# Con_Mic_Module_no_gain.net
KiCad netlist of a schematic drawn in Altium Designer
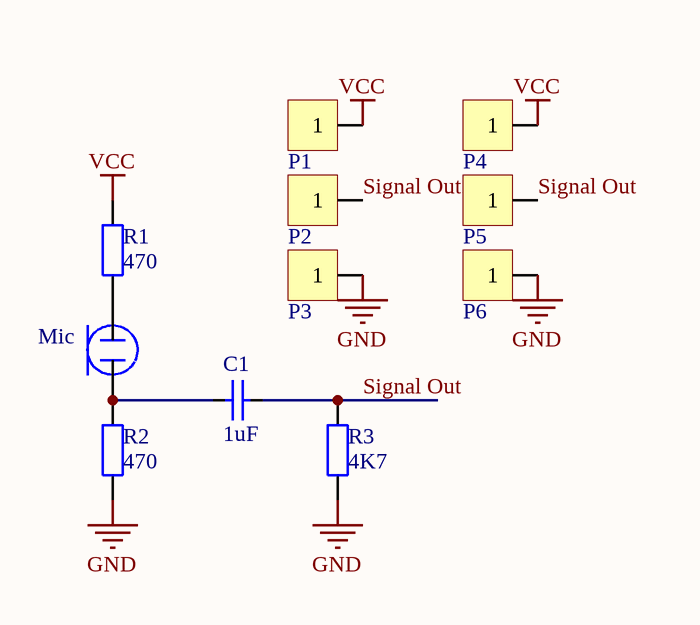
[diagram p0: Con_Mic_Module(no gain).SchDoc]

(export (version "E")
  (design (tool "Eeschema 10.0.6"))
  (components
    (comp (ref "C1")
      (value "1uF")
      (footprint "CAP_0805")
      (description "Capacitor")
      (fields (field (name "Comment") "Cap_0805"))
      (libsource (lib "Integrated_Library") (part "Cap_0805"))
    )
    (comp (ref "Mic")
      (value "Mic")
      (footprint "Con_Mic_9.6mm")
      (description "Condenser Microphone")
      (libsource (lib "Integrated_Library") (part "Con_Mic_9.7mm"))
    )
    (comp (ref "P1")
      (value "Pad1X1_1.27")
      (footprint "Pad1X1_1.27")
      (description "Header")
      (libsource (lib "Integrated_Library") (part "Pad1X1_1.27"))
    )
    (comp (ref "P2")
      (value "Pad1X1_1.27")
      (footprint "Pad1X1_1.27")
      (description "Header")
      (libsource (lib "Integrated_Library") (part "Pad1X1_1.27"))
    )
    (comp (ref "P3")
      (value "Pad1X1_1.27")
      (footprint "Pad1X1_1.27")
      (description "Header")
      (libsource (lib "Integrated_Library") (part "Pad1X1_1.27"))
    )
    (comp (ref "P4")
      (value "HDR1X1_180_2.54")
      (footprint "HDR1X1_180_2.54")
      (description "Header")
      (libsource (lib "Integrated_Library") (part "HDR1X1_180_2.54"))
    )
    (comp (ref "P5")
      (value "HDR1X1_180_2.54")
      (footprint "HDR1X1_180_2.54")
      (description "Header")
      (libsource (lib "Integrated_Library") (part "HDR1X1_180_2.54"))
    )
    (comp (ref "P6")
      (value "HDR1X1_180_2.54")
      (footprint "HDR1X1_180_2.54")
      (description "Header")
      (libsource (lib "Integrated_Library") (part "HDR1X1_180_2.54"))
    )
    (comp (ref "R1")
      (value "470")
      (footprint "RES_0805")
      (description "Resistor")
      (fields (field (name "Comment") "Res_0805"))
      (libsource (lib "Integrated_Library") (part "Res_0805"))
    )
    (comp (ref "R2")
      (value "470")
      (footprint "RES_0805")
      (description "Resistor")
      (fields (field (name "Comment") "Res_0805"))
      (libsource (lib "Integrated_Library") (part "Res_0805"))
    )
    (comp (ref "R3")
      (value "4K7")
      (footprint "RES_0805")
      (description "Resistor")
      (fields (field (name "Comment") "Res_0805"))
      (libsource (lib "Integrated_Library") (part "Res_0805"))
    )
  )
  (nets
    (net (code "1") (name "/Signal Out") (class "Default")
      (node (ref "C1") (pin "2") (pinfunction "2_2") (pintype "passive"))
      (node (ref "P2") (pin "1") (pinfunction "1_1") (pintype "passive"))
      (node (ref "P5") (pin "1") (pinfunction "1_1") (pintype "passive"))
      (node (ref "R3") (pin "2") (pinfunction "2_2") (pintype "passive"))
    )
    (net (code "2") (name "GND") (class "Default")
      (node (ref "P3") (pin "1") (pinfunction "1_1") (pintype "passive"))
      (node (ref "P6") (pin "1") (pinfunction "1_1") (pintype "passive"))
      (node (ref "R2") (pin "1") (pinfunction "1_1") (pintype "passive"))
      (node (ref "R3") (pin "1") (pinfunction "1_1") (pintype "passive"))
    )
    (net (code "3") (name "Net-(Mic-FlexiblePlat)") (class "Default")
      (node (ref "Mic") (pin "1") (pinfunction "FlexiblePlat_1") (pintype "passive"))
      (node (ref "R1") (pin "1") (pinfunction "1_1") (pintype "passive"))
    )
    (net (code "4") (name "Net-(Mic-RigidPlat)") (class "Default")
      (node (ref "C1") (pin "1") (pinfunction "1_1") (pintype "passive"))
      (node (ref "Mic") (pin "2") (pinfunction "RigidPlat_2") (pintype "passive"))
      (node (ref "R2") (pin "2") (pinfunction "2_2") (pintype "passive"))
    )
    (net (code "5") (name "VCC") (class "Default")
      (node (ref "P1") (pin "1") (pinfunction "1_1") (pintype "passive"))
      (node (ref "P4") (pin "1") (pinfunction "1_1") (pintype "passive"))
      (node (ref "R1") (pin "2") (pinfunction "2_2") (pintype "passive"))
    )
  )
)
